# Driver_Board_Schematics.net
KiCad netlist of a schematic drawn in EAGLE
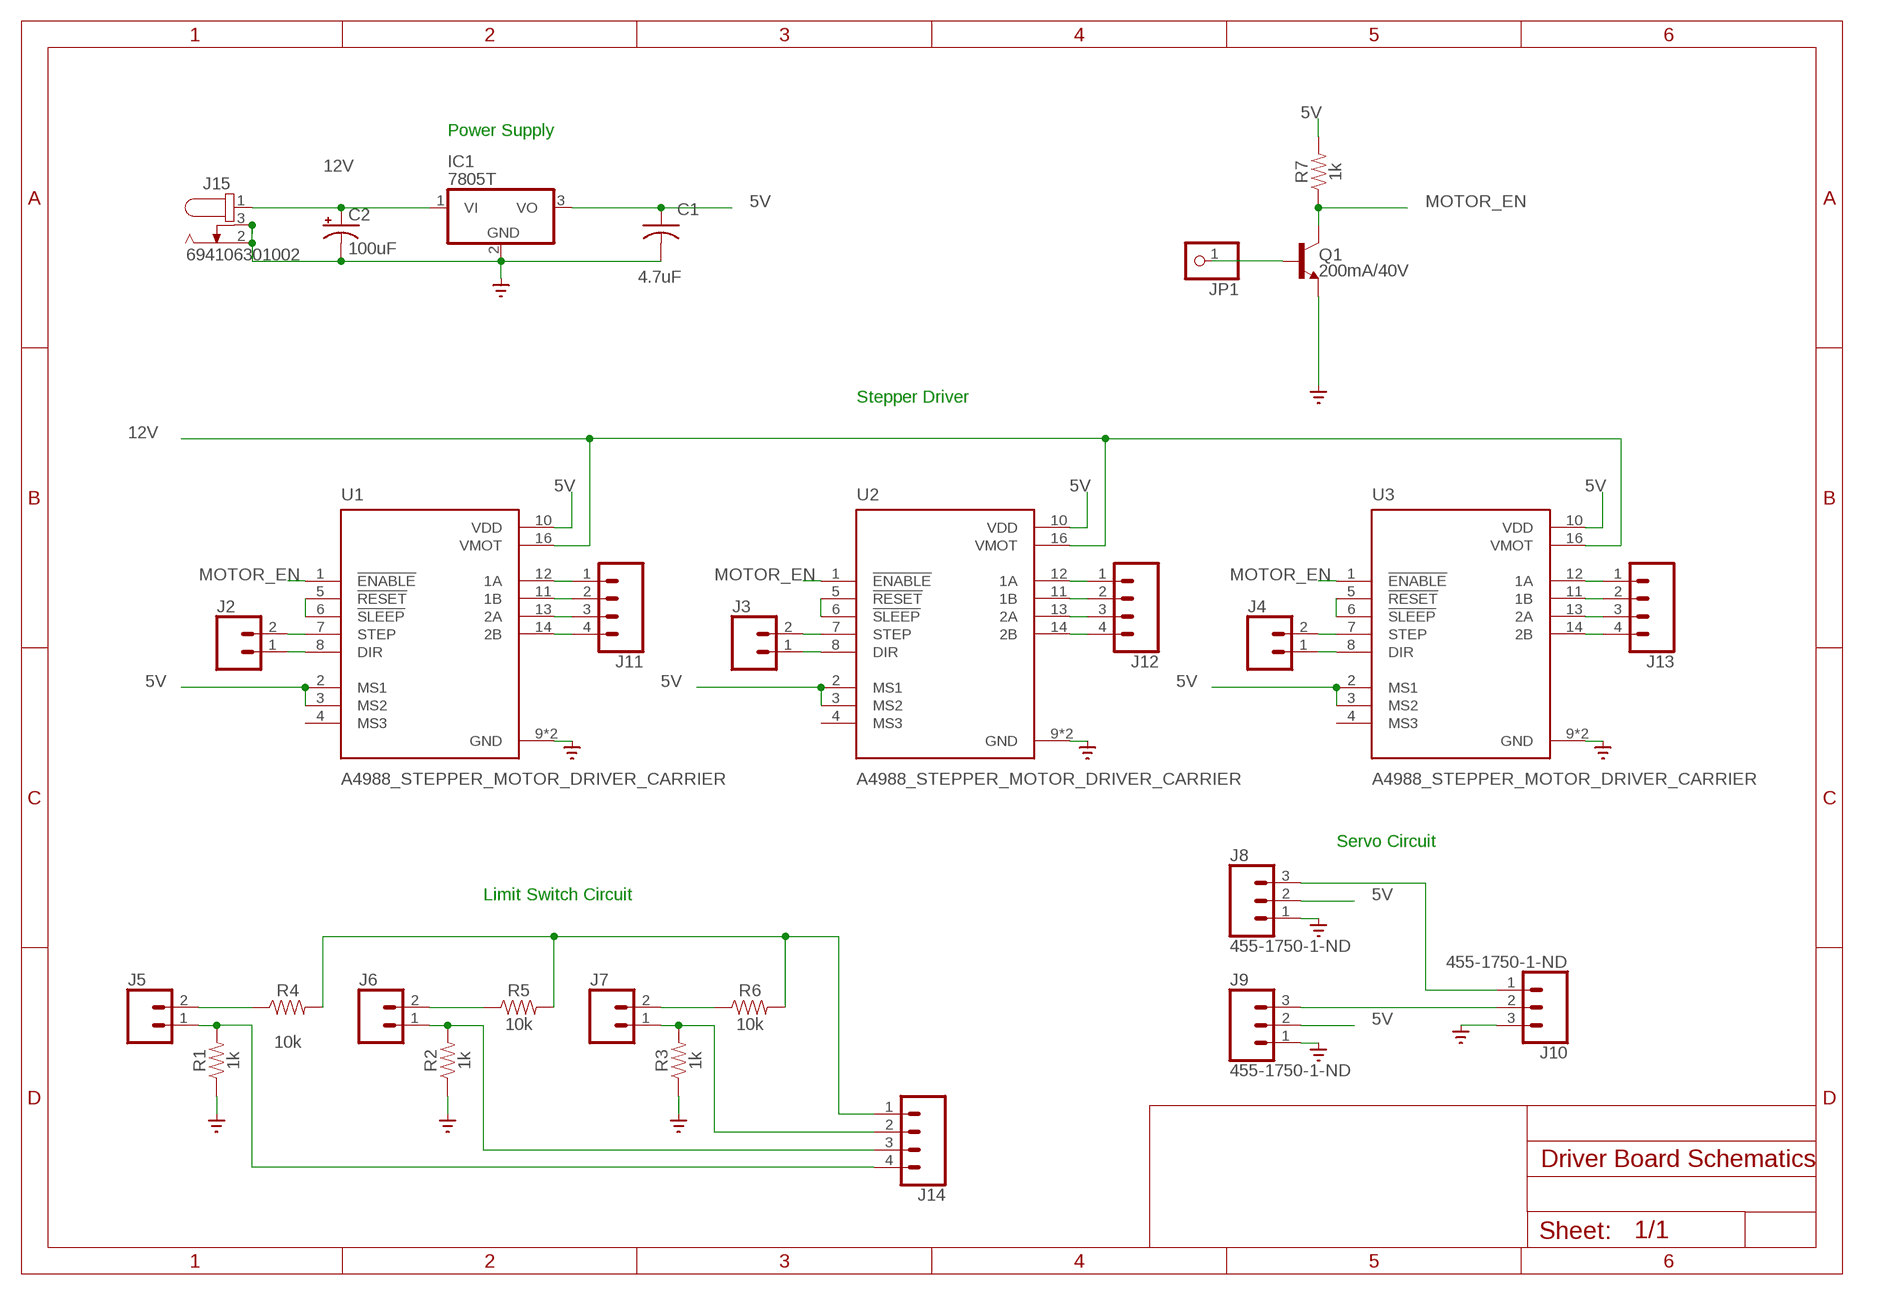
[diagram p0: schematic, sheet 1]

(export (version "E")
  (design (tool "Eeschema 10.0.6"))
  (components
    (comp (ref "C1")
      (value "4.7uF")
      (footprint "eagle-import:CAP_RADIAL_2MM")
      (fields
        (field (name "DIGIKEY_PART_NUMBER") "P5177-ND")
        (field (name "MANUFACTURER") "Panasonic Electronic Components")
        (field (name "MPN") "ECA-1HM4R7")
        (field (name "CREATED_BY") "PCBLayout.com")
      )
      (libsource (lib "eagle-import") (part "ECA-1HM4R7"))
    )
    (comp (ref "C2")
      (value "100uF")
      (footprint "eagle-import:CPOL-RADIAL-2.5MM-6.5MM")
      (libsource (lib "eagle-import") (part "100UF-POLAR-RADIAL-2.5MM-25V-20%"))
    )
    (comp (ref "IC1")
      (value "7805T")
      (footprint "eagle-import:TO220H")
      (libsource (lib "eagle-import") (part "78T05"))
    )
    (comp (ref "J2")
      (value "CONN_02")
      (footprint "eagle-import:1X02")
      (libsource (lib "eagle-import") (part "CONN_02"))
    )
    (comp (ref "J3")
      (value "CONN_02")
      (footprint "eagle-import:1X02")
      (libsource (lib "eagle-import") (part "CONN_02"))
    )
    (comp (ref "J4")
      (value "CONN_02")
      (footprint "eagle-import:1X02")
      (libsource (lib "eagle-import") (part "CONN_02"))
    )
    (comp (ref "J5")
      (value "CONN_02")
      (footprint "eagle-import:1X02")
      (libsource (lib "eagle-import") (part "CONN_02"))
    )
    (comp (ref "J6")
      (value "CONN_02")
      (footprint "eagle-import:1X02")
      (libsource (lib "eagle-import") (part "CONN_02"))
    )
    (comp (ref "J7")
      (value "CONN_02")
      (footprint "eagle-import:1X02")
      (libsource (lib "eagle-import") (part "CONN_02"))
    )
    (comp (ref "J8")
      (value "455-1750-1-ND")
      (footprint "eagle-import:1X03")
      (libsource (lib "eagle-import") (part "CONN_03"))
    )
    (comp (ref "J9")
      (value "455-1750-1-ND")
      (footprint "eagle-import:1X03")
      (libsource (lib "eagle-import") (part "CONN_03"))
    )
    (comp (ref "J10")
      (value "455-1750-1-ND")
      (footprint "eagle-import:1X03")
      (libsource (lib "eagle-import") (part "CONN_03"))
    )
    (comp (ref "J11")
      (value "CONN_04PTH")
      (footprint "eagle-import:1X04")
      (libsource (lib "eagle-import") (part "CONN_04PTH"))
    )
    (comp (ref "J12")
      (value "CONN_04PTH")
      (footprint "eagle-import:1X04")
      (libsource (lib "eagle-import") (part "CONN_04PTH"))
    )
    (comp (ref "J13")
      (value "CONN_04PTH")
      (footprint "eagle-import:1X04")
      (libsource (lib "eagle-import") (part "CONN_04PTH"))
    )
    (comp (ref "J14")
      (value "CONN_04PTH")
      (footprint "eagle-import:1X04")
      (libsource (lib "eagle-import") (part "CONN_04PTH"))
    )
    (comp (ref "J15")
      (value "694106301002")
      (footprint "eagle-import:694106301002")
      (libsource (lib "eagle-import") (part "694106301002"))
    )
    (comp (ref "JP1")
      (value "PINHD-1X1")
      (footprint "eagle-import:1X01")
      (libsource (lib "eagle-import") (part "PINHD-1X1"))
    )
    (comp (ref "Q1")
      (value "200mA/40V")
      (footprint "eagle-import:TO-92")
      (libsource (lib "eagle-import") (part "TRANS_NPN-2N3904"))
    )
    (comp (ref "R1")
      (value "1k")
      (footprint "eagle-import:AXIAL-0.3")
      (libsource (lib "eagle-import") (part "1KOHM-HORIZ-1/4W-1%"))
    )
    (comp (ref "R2")
      (value "1k")
      (footprint "eagle-import:AXIAL-0.3")
      (libsource (lib "eagle-import") (part "1KOHM-HORIZ-1/4W-1%"))
    )
    (comp (ref "R3")
      (value "1k")
      (footprint "eagle-import:AXIAL-0.3")
      (libsource (lib "eagle-import") (part "1KOHM-HORIZ-1/4W-1%"))
    )
    (comp (ref "R4")
      (value "10k")
      (footprint "eagle-import:AXIAL-0.3")
      (libsource (lib "eagle-import") (part "10KOHM-HORIZ-1/4W-1%"))
    )
    (comp (ref "R5")
      (value "10k")
      (footprint "eagle-import:AXIAL-0.3")
      (libsource (lib "eagle-import") (part "10KOHM-HORIZ-1/4W-1%"))
    )
    (comp (ref "R6")
      (value "10k")
      (footprint "eagle-import:AXIAL-0.3")
      (libsource (lib "eagle-import") (part "10KOHM-HORIZ-1/4W-1%"))
    )
    (comp (ref "R7")
      (value "1k")
      (footprint "eagle-import:AXIAL-0.3")
      (libsource (lib "eagle-import") (part "1KOHM-HORIZ-1/4W-1%"))
    )
    (comp (ref "U1")
      (value "A4988_STEPPER_MOTOR_DRIVER_CARRIER")
      (footprint "eagle-import:MODULE_A4988_STEPPER_MOTOR_DRIVER_CARRIER")
      (fields (field (name "MF") "Pololu") (field (name "MP") "A4988 STEPPER MOTOR DRIVER CARRIER"))
      (libsource (lib "eagle-import") (part "A4988_STEPPER_MOTOR_DRIVER_CARRIER"))
    )
    (comp (ref "U2")
      (value "A4988_STEPPER_MOTOR_DRIVER_CARRIER")
      (footprint "eagle-import:MODULE_A4988_STEPPER_MOTOR_DRIVER_CARRIER")
      (fields (field (name "MF") "Pololu") (field (name "MP") "A4988 STEPPER MOTOR DRIVER CARRIER"))
      (libsource (lib "eagle-import") (part "A4988_STEPPER_MOTOR_DRIVER_CARRIER"))
    )
    (comp (ref "U3")
      (value "A4988_STEPPER_MOTOR_DRIVER_CARRIER")
      (footprint "eagle-import:MODULE_A4988_STEPPER_MOTOR_DRIVER_CARRIER")
      (fields (field (name "MF") "Pololu") (field (name "MP") "A4988 STEPPER MOTOR DRIVER CARRIER"))
      (libsource (lib "eagle-import") (part "A4988_STEPPER_MOTOR_DRIVER_CARRIER"))
    )
  )
  (nets
    (net (code "1") (name "/5V") (class "Default")
      (node (ref "C1") (pin "1") (pinfunction "1_1") (pintype "passive"))
      (node (ref "IC1") (pin "3") (pinfunction "VO_3") (pintype "passive"))
      (node (ref "J8") (pin "2") (pinfunction "2_2") (pintype "passive"))
      (node (ref "J9") (pin "2") (pinfunction "2_2") (pintype "passive"))
      (node (ref "R7") (pin "P$2") (pinfunction "2_P$2") (pintype "passive"))
      (node (ref "U1") (pin "10") (pinfunction "VDD_10") (pintype "power_in"))
      (node (ref "U1") (pin "2") (pinfunction "MS1_2") (pintype "input"))
      (node (ref "U1") (pin "3") (pinfunction "MS2_3") (pintype "input"))
      (node (ref "U2") (pin "10") (pinfunction "VDD_10") (pintype "power_in"))
      (node (ref "U2") (pin "2") (pinfunction "MS1_2") (pintype "input"))
      (node (ref "U2") (pin "3") (pinfunction "MS2_3") (pintype "input"))
      (node (ref "U3") (pin "10") (pinfunction "VDD_10") (pintype "power_in"))
      (node (ref "U3") (pin "2") (pinfunction "MS1_2") (pintype "input"))
      (node (ref "U3") (pin "3") (pinfunction "MS2_3") (pintype "input"))
    )
    (net (code "2") (name "/12V") (class "Default")
      (node (ref "C2") (pin "1") (pinfunction "+_1") (pintype "passive"))
      (node (ref "IC1") (pin "1") (pinfunction "VI_1") (pintype "input"))
      (node (ref "J15") (pin "1") (pinfunction "1_1") (pintype "passive"))
      (node (ref "U1") (pin "16") (pinfunction "VMOT_16") (pintype "power_in"))
      (node (ref "U2") (pin "16") (pinfunction "VMOT_16") (pintype "power_in"))
      (node (ref "U3") (pin "16") (pinfunction "VMOT_16") (pintype "power_in"))
    )
    (net (code "3") (name "/MOTOR_EN") (class "Default")
      (node (ref "Q1") (pin "3") (pinfunction "C_3") (pintype "passive"))
      (node (ref "R7") (pin "P$1") (pinfunction "1_P$1") (pintype "passive"))
      (node (ref "U1") (pin "1") (pinfunction "~{ENABLE}_1") (pintype "input"))
      (node (ref "U2") (pin "1") (pinfunction "~{ENABLE}_1") (pintype "input"))
      (node (ref "U3") (pin "1") (pinfunction "~{ENABLE}_1") (pintype "input"))
    )
    (net (code "4") (name "Net-(J10-Pad1)") (class "Default")
      (node (ref "J10") (pin "1") (pinfunction "1_1") (pintype "passive"))
      (node (ref "J8") (pin "3") (pinfunction "3_3") (pintype "passive"))
    )
    (net (code "5") (name "Net-(J10-Pad2)") (class "Default")
      (node (ref "J10") (pin "2") (pinfunction "2_2") (pintype "passive"))
      (node (ref "J9") (pin "3") (pinfunction "3_3") (pintype "passive"))
    )
    (net (code "6") (name "Net-(Q1-B)") (class "Default")
      (node (ref "JP1") (pin "1") (pinfunction "1_1") (pintype "passive"))
      (node (ref "Q1") (pin "2") (pinfunction "B_2") (pintype "passive"))
    )
    (net (code "7") (name "Net-(R1-2)") (class "Default")
      (node (ref "J14") (pin "4") (pinfunction "4_4") (pintype "passive"))
      (node (ref "J5") (pin "1") (pinfunction "1_1") (pintype "passive"))
      (node (ref "R1") (pin "P$2") (pinfunction "2_P$2") (pintype "passive"))
    )
    (net (code "8") (name "Net-(R2-2)") (class "Default")
      (node (ref "J14") (pin "3") (pinfunction "3_3") (pintype "passive"))
      (node (ref "J6") (pin "1") (pinfunction "1_1") (pintype "passive"))
      (node (ref "R2") (pin "P$2") (pinfunction "2_P$2") (pintype "passive"))
    )
    (net (code "9") (name "Net-(R3-2)") (class "Default")
      (node (ref "J14") (pin "2") (pinfunction "2_2") (pintype "passive"))
      (node (ref "J7") (pin "1") (pinfunction "1_1") (pintype "passive"))
      (node (ref "R3") (pin "P$2") (pinfunction "2_P$2") (pintype "passive"))
    )
    (net (code "10") (name "Net-(R4-1)") (class "Default")
      (node (ref "J5") (pin "2") (pinfunction "2_2") (pintype "passive"))
      (node (ref "R4") (pin "P$1") (pinfunction "1_P$1") (pintype "passive"))
    )
    (net (code "11") (name "Net-(R4-2)") (class "Default")
      (node (ref "J14") (pin "1") (pinfunction "1_1") (pintype "passive"))
      (node (ref "R4") (pin "P$2") (pinfunction "2_P$2") (pintype "passive"))
      (node (ref "R5") (pin "P$2") (pinfunction "2_P$2") (pintype "passive"))
      (node (ref "R6") (pin "P$2") (pinfunction "2_P$2") (pintype "passive"))
    )
    (net (code "12") (name "Net-(R5-1)") (class "Default")
      (node (ref "J6") (pin "2") (pinfunction "2_2") (pintype "passive"))
      (node (ref "R5") (pin "P$1") (pinfunction "1_P$1") (pintype "passive"))
    )
    (net (code "13") (name "Net-(R6-1)") (class "Default")
      (node (ref "J7") (pin "2") (pinfunction "2_2") (pintype "passive"))
      (node (ref "R6") (pin "P$1") (pinfunction "1_P$1") (pintype "passive"))
    )
    (net (code "14") (name "Net-(U1-1A)") (class "Default")
      (node (ref "J11") (pin "1") (pinfunction "1_1") (pintype "passive"))
      (node (ref "U1") (pin "12") (pinfunction "1A_12") (pintype "output"))
    )
    (net (code "15") (name "Net-(U1-1B)") (class "Default")
      (node (ref "J11") (pin "2") (pinfunction "2_2") (pintype "passive"))
      (node (ref "U1") (pin "11") (pinfunction "1B_11") (pintype "output"))
    )
    (net (code "16") (name "Net-(U1-2A)") (class "Default")
      (node (ref "J11") (pin "3") (pinfunction "3_3") (pintype "passive"))
      (node (ref "U1") (pin "13") (pinfunction "2A_13") (pintype "output"))
    )
    (net (code "17") (name "Net-(U1-2B)") (class "Default")
      (node (ref "J11") (pin "4") (pinfunction "4_4") (pintype "passive"))
      (node (ref "U1") (pin "14") (pinfunction "2B_14") (pintype "output"))
    )
    (net (code "18") (name "Net-(U1-DIR)") (class "Default")
      (node (ref "J2") (pin "1") (pinfunction "1_1") (pintype "passive"))
      (node (ref "U1") (pin "8") (pinfunction "DIR_8") (pintype "input"))
    )
    (net (code "19") (name "Net-(U1-STEP)") (class "Default")
      (node (ref "J2") (pin "2") (pinfunction "2_2") (pintype "passive"))
      (node (ref "U1") (pin "7") (pinfunction "STEP_7") (pintype "input"))
    )
    (net (code "20") (name "Net-(U1-~{RESET})") (class "Default")
      (node (ref "U1") (pin "5") (pinfunction "~{RESET}_5") (pintype "input"))
      (node (ref "U1") (pin "6") (pinfunction "~{SLEEP}_6") (pintype "input"))
    )
    (net (code "21") (name "Net-(U2-1A)") (class "Default")
      (node (ref "J12") (pin "1") (pinfunction "1_1") (pintype "passive"))
      (node (ref "U2") (pin "12") (pinfunction "1A_12") (pintype "output"))
    )
    (net (code "22") (name "Net-(U2-1B)") (class "Default")
      (node (ref "J12") (pin "2") (pinfunction "2_2") (pintype "passive"))
      (node (ref "U2") (pin "11") (pinfunction "1B_11") (pintype "output"))
    )
    (net (code "23") (name "Net-(U2-2A)") (class "Default")
      (node (ref "J12") (pin "3") (pinfunction "3_3") (pintype "passive"))
      (node (ref "U2") (pin "13") (pinfunction "2A_13") (pintype "output"))
    )
    (net (code "24") (name "Net-(U2-2B)") (class "Default")
      (node (ref "J12") (pin "4") (pinfunction "4_4") (pintype "passive"))
      (node (ref "U2") (pin "14") (pinfunction "2B_14") (pintype "output"))
    )
    (net (code "25") (name "Net-(U2-DIR)") (class "Default")
      (node (ref "J3") (pin "1") (pinfunction "1_1") (pintype "passive"))
      (node (ref "U2") (pin "8") (pinfunction "DIR_8") (pintype "input"))
    )
    (net (code "26") (name "Net-(U2-STEP)") (class "Default")
      (node (ref "J3") (pin "2") (pinfunction "2_2") (pintype "passive"))
      (node (ref "U2") (pin "7") (pinfunction "STEP_7") (pintype "input"))
    )
    (net (code "27") (name "Net-(U2-~{RESET})") (class "Default")
      (node (ref "U2") (pin "5") (pinfunction "~{RESET}_5") (pintype "input"))
      (node (ref "U2") (pin "6") (pinfunction "~{SLEEP}_6") (pintype "input"))
    )
    (net (code "28") (name "Net-(U3-1A)") (class "Default")
      (node (ref "J13") (pin "1") (pinfunction "1_1") (pintype "passive"))
      (node (ref "U3") (pin "12") (pinfunction "1A_12") (pintype "output"))
    )
    (net (code "29") (name "Net-(U3-1B)") (class "Default")
      (node (ref "J13") (pin "2") (pinfunction "2_2") (pintype "passive"))
      (node (ref "U3") (pin "11") (pinfunction "1B_11") (pintype "output"))
    )
    (net (code "30") (name "Net-(U3-2A)") (class "Default")
      (node (ref "J13") (pin "3") (pinfunction "3_3") (pintype "passive"))
      (node (ref "U3") (pin "13") (pinfunction "2A_13") (pintype "output"))
    )
    (net (code "31") (name "Net-(U3-2B)") (class "Default")
      (node (ref "J13") (pin "4") (pinfunction "4_4") (pintype "passive"))
      (node (ref "U3") (pin "14") (pinfunction "2B_14") (pintype "output"))
    )
    (net (code "32") (name "Net-(U3-DIR)") (class "Default")
      (node (ref "J4") (pin "1") (pinfunction "1_1") (pintype "passive"))
      (node (ref "U3") (pin "8") (pinfunction "DIR_8") (pintype "input"))
    )
    (net (code "33") (name "Net-(U3-STEP)") (class "Default")
      (node (ref "J4") (pin "2") (pinfunction "2_2") (pintype "passive"))
      (node (ref "U3") (pin "7") (pinfunction "STEP_7") (pintype "input"))
    )
    (net (code "34") (name "Net-(U3-~{RESET})") (class "Default")
      (node (ref "U3") (pin "5") (pinfunction "~{RESET}_5") (pintype "input"))
      (node (ref "U3") (pin "6") (pinfunction "~{SLEEP}_6") (pintype "input"))
    )
    (net (code "35") (name "SUPPLY0_GND_") (class "Default")
      (node (ref "C1") (pin "2") (pinfunction "2_2") (pintype "passive"))
      (node (ref "C2") (pin "2") (pinfunction "-_2") (pintype "passive"))
      (node (ref "IC1") (pin "2") (pinfunction "GND_2") (pintype "passive"))
      (node (ref "J10") (pin "3") (pinfunction "3_3") (pintype "passive"))
      (node (ref "J15") (pin "2") (pinfunction "2_2") (pintype "passive"))
      (node (ref "J15") (pin "3") (pinfunction "3_3") (pintype "passive"))
      (node (ref "J8") (pin "1") (pinfunction "1_1") (pintype "passive"))
      (node (ref "J9") (pin "1") (pinfunction "1_1") (pintype "passive"))
      (node (ref "Q1") (pin "1") (pinfunction "E_1") (pintype "passive"))
      (node (ref "R1") (pin "P$1") (pinfunction "1_P$1") (pintype "passive"))
      (node (ref "R2") (pin "P$1") (pinfunction "1_P$1") (pintype "passive"))
      (node (ref "R3") (pin "P$1") (pinfunction "1_P$1") (pintype "passive"))
      (node (ref "U1") (pin "15") (pinfunction "GND_15") (pintype "power_in"))
      (node (ref "U1") (pin "9") (pinfunction "GND_9") (pintype "power_in"))
      (node (ref "U2") (pin "15") (pinfunction "GND_15") (pintype "power_in"))
      (node (ref "U2") (pin "9") (pinfunction "GND_9") (pintype "power_in"))
      (node (ref "U3") (pin "15") (pinfunction "GND_15") (pintype "power_in"))
      (node (ref "U3") (pin "9") (pinfunction "GND_9") (pintype "power_in"))
    )
    (net (code "36") (name "unconnected-(U1-MS3-Pad4)") (class "Default")
      (node (ref "U1") (pin "4") (pinfunction "MS3_4") (pintype "input"))
    )
    (net (code "37") (name "unconnected-(U2-MS3-Pad4)") (class "Default")
      (node (ref "U2") (pin "4") (pinfunction "MS3_4") (pintype "input"))
    )
    (net (code "38") (name "unconnected-(U3-MS3-Pad4)") (class "Default")
      (node (ref "U3") (pin "4") (pinfunction "MS3_4") (pintype "input"))
    )
  )
)
